# binary_watch.net
KiCad netlist of a schematic drawn in EAGLE
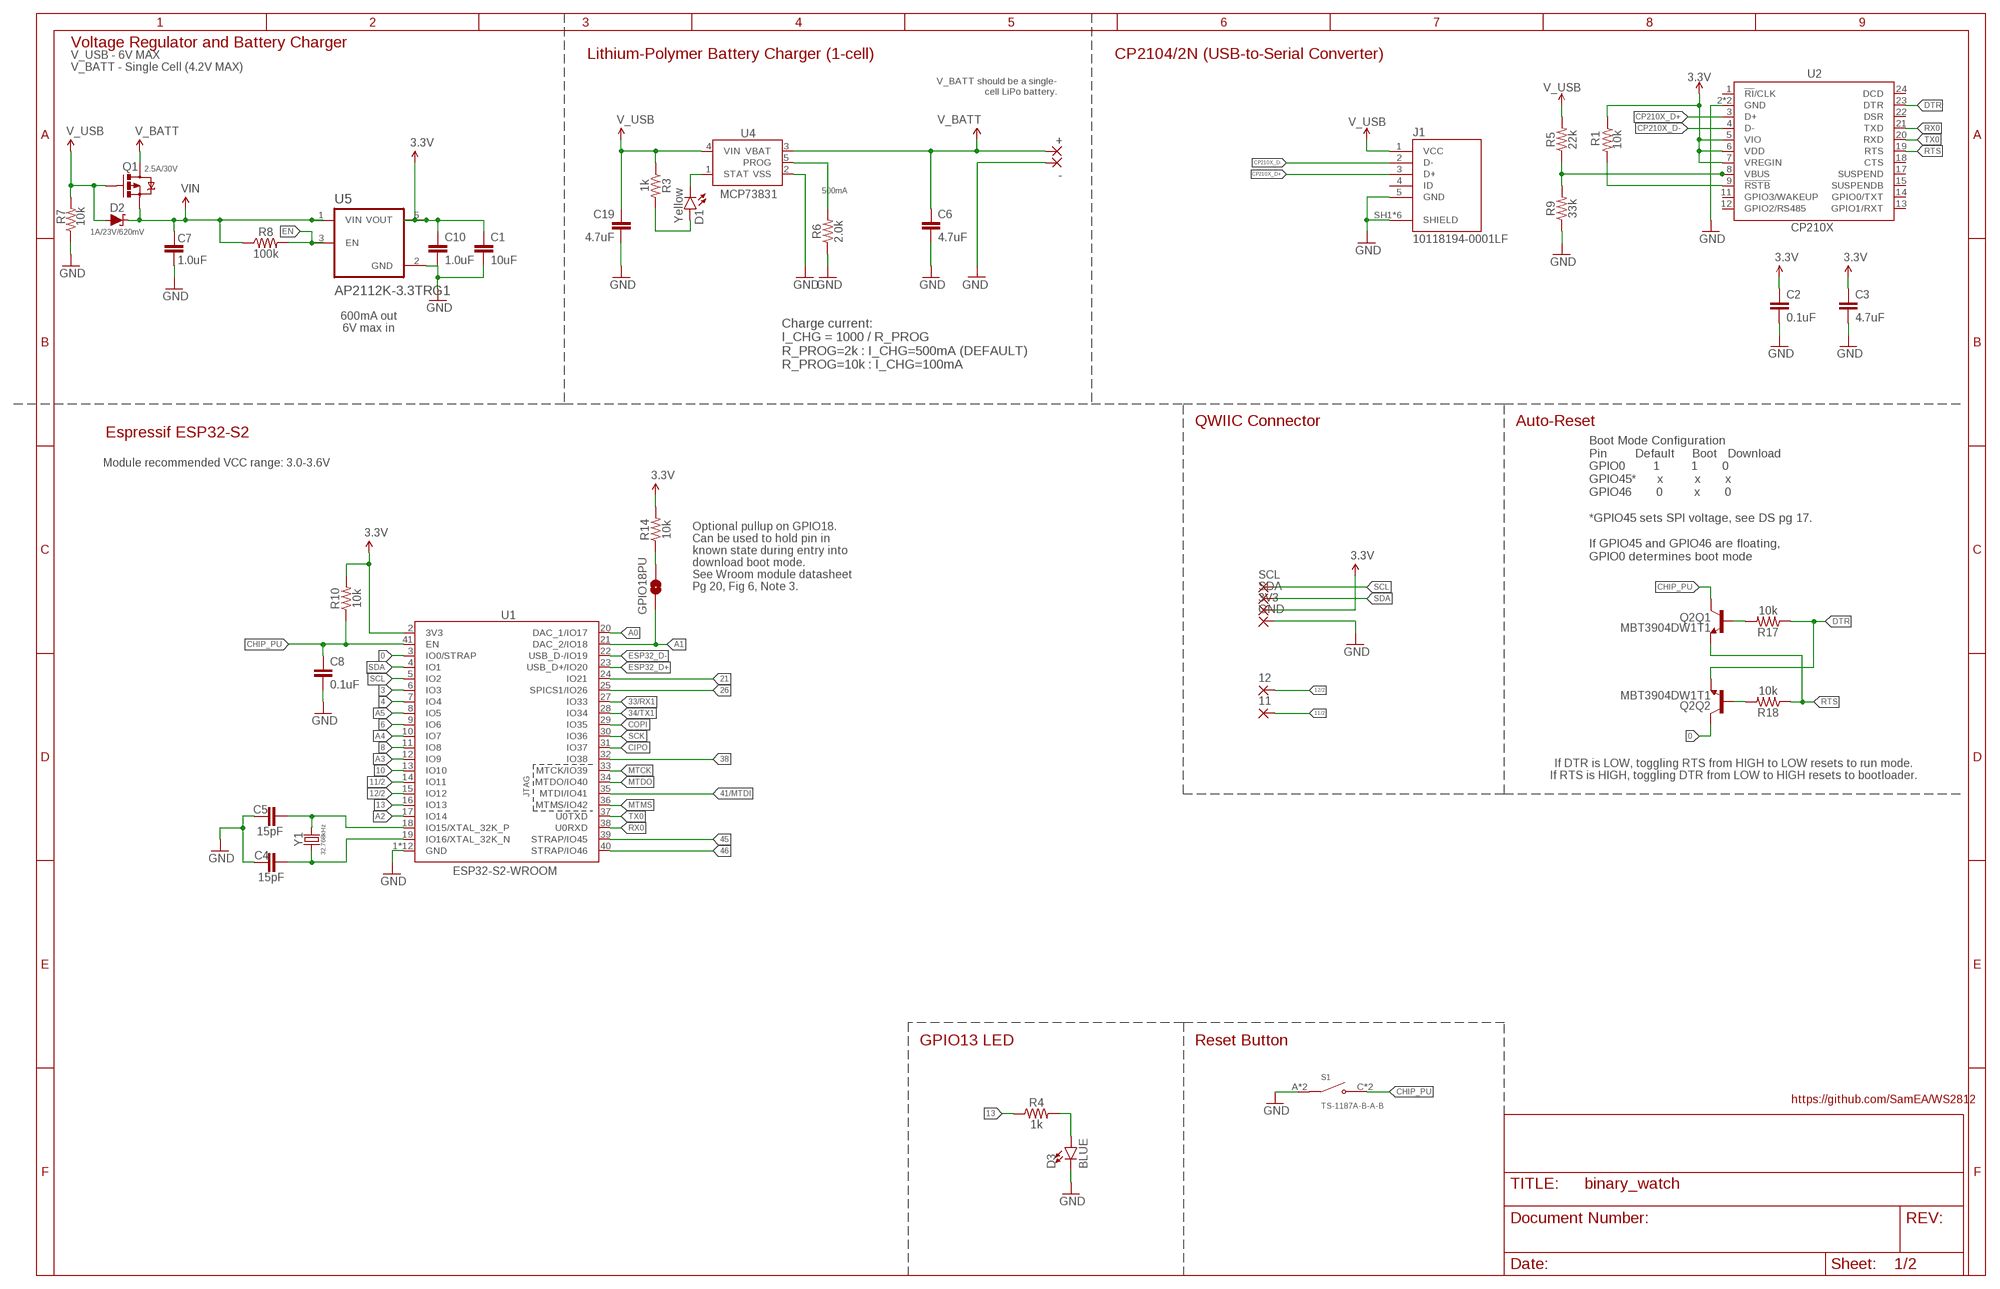
[diagram p0: schematic, sheet 1]
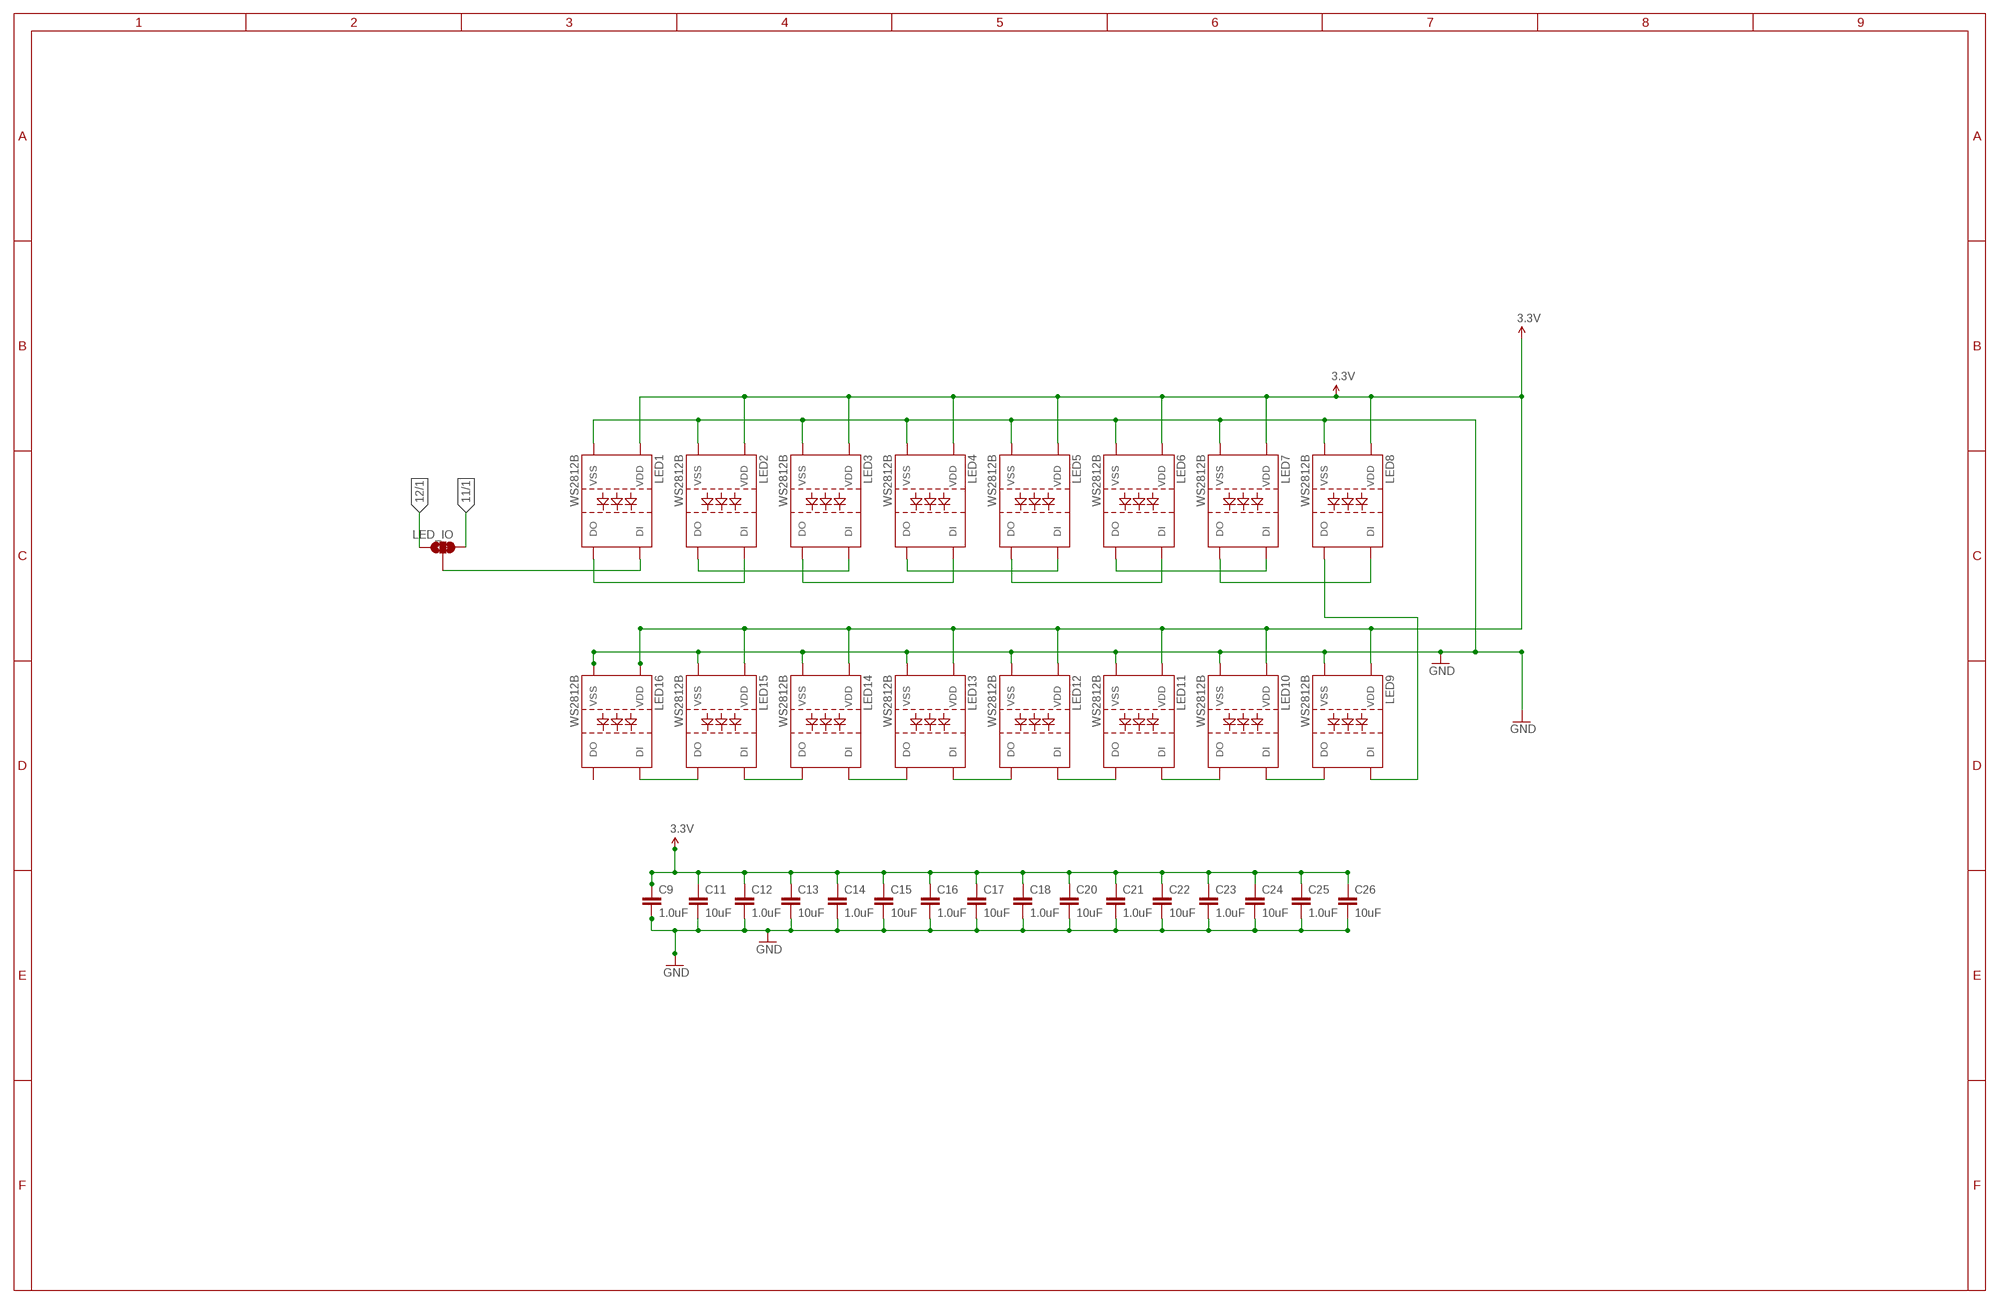
[diagram p1: schematic, sheet 2]

(export (version "E")
  (design (tool "Eeschema 10.0.6"))
  (components
    (comp (ref "+")
      (value "WIREPAD1,6/0,8")
      (footprint "eagle-import:1,6_0,8")
      (libsource (lib "eagle-import") (part "WIREPAD1,6/0,8"))
    )
    (comp (ref "-")
      (value "WIREPAD1,6/0,8")
      (footprint "eagle-import:1,6_0,8")
      (libsource (lib "eagle-import") (part "WIREPAD1,6/0,8"))
    )
    (comp (ref "3V3")
      (value "1,6/0,8")
      (footprint "eagle-import:1,6_0,8")
      (libsource (lib "eagle-import") (part "1,6/0,8"))
    )
    (comp (ref "11")
      (value "1,6/0,8")
      (footprint "eagle-import:1,6_0,8")
      (libsource (lib "eagle-import") (part "1,6/0,8"))
    )
    (comp (ref "12")
      (value "1,6/0,8")
      (footprint "eagle-import:1,6_0,8")
      (libsource (lib "eagle-import") (part "1,6/0,8"))
    )
    (comp (ref "C1")
      (value "10uF")
      (footprint "eagle-import:0402-TIGHT")
      (libsource (lib "eagle-import") (part "10UF-0402T-6.3V-20%"))
    )
    (comp (ref "C2")
      (value "0.1uF")
      (footprint "eagle-import:0402-TIGHT")
      (libsource (lib "eagle-import") (part "0.1UF-0402T-16V-10%"))
    )
    (comp (ref "C3")
      (value "4.7uF")
      (footprint "eagle-import:0402-TIGHT")
      (libsource (lib "eagle-import") (part "4.7UF-0402_TIGHT-6.3V-20%-X5R"))
    )
    (comp (ref "C4")
      (value "15pF")
      (footprint "eagle-import:0402-TIGHT")
      (libsource (lib "eagle-import") (part "15PF-0402T-50V-5%"))
    )
    (comp (ref "C5")
      (value "15pF")
      (footprint "eagle-import:0402-TIGHT")
      (libsource (lib "eagle-import") (part "15PF-0402T-50V-5%"))
    )
    (comp (ref "C6")
      (value "4.7uF")
      (footprint "eagle-import:0402-TIGHT")
      (libsource (lib "eagle-import") (part "4.7UF-0402_TIGHT-6.3V-20%-X5R"))
    )
    (comp (ref "C7")
      (value "1.0uF")
      (footprint "eagle-import:0402-TIGHT")
      (libsource (lib "eagle-import") (part "1.0UF-0402T-16V-10%"))
    )
    (comp (ref "C8")
      (value "0.1uF")
      (footprint "eagle-import:0402-TIGHT")
      (libsource (lib "eagle-import") (part "0.1UF-0402T-16V-10%"))
    )
    (comp (ref "C10")
      (value "1.0uF")
      (footprint "eagle-import:0402-TIGHT")
      (libsource (lib "eagle-import") (part "1.0UF-0402T-16V-10%"))
    )
    (comp (ref "C19")
      (value "4.7uF")
      (footprint "eagle-import:0402-TIGHT")
      (libsource (lib "eagle-import") (part "4.7UF-0402_TIGHT-6.3V-20%-X5R"))
    )
    (comp (ref "D1")
      (value "Yellow")
      (footprint "eagle-import:LED-0603")
      (libsource (lib "eagle-import") (part "LED-YELLOW0603"))
    )
    (comp (ref "D2")
      (value "1A/23V/620mV")
      (footprint "eagle-import:SOD-323")
      (libsource (lib "eagle-import") (part "DIODE-SCHOTTKY-BAT20J"))
    )
    (comp (ref "D3")
      (value "BLUE")
      (footprint "eagle-import:LED-0603")
      (libsource (lib "eagle-import") (part "LED-BLUE0603"))
    )
    (comp (ref "GND")
      (value "1,6/0,8")
      (footprint "eagle-import:1,6_0,8")
      (libsource (lib "eagle-import") (part "1,6/0,8"))
    )
    (comp (ref "GPIO18PU")
      (value "JUMPER-SMT_2_NO_SILK")
      (footprint "eagle-import:SMT-JUMPER_2_NO_SILK")
      (libsource (lib "eagle-import") (part "JUMPER-SMT_2_NO_SILK"))
    )
    (comp (ref "J1")
      (value "10118194-0001LF")
      (footprint "eagle-import:AMPHENOL_10118194-0001LF")
      (fields (field (name "MF") "Amphenol ICC"))
      (libsource (lib "eagle-import") (part "10118194-0001LF"))
    )
    (comp (ref "Q1")
      (value "2.5A/30V")
      (footprint "eagle-import:SOT23-3@1")
      (libsource (lib "eagle-import") (part "MOSFET-PCHANNELDMG2307L"))
    )
    (comp (ref "Q2")
      (value "MBT3904DW1T1")
      (footprint "eagle-import:SC70-6")
      (libsource (lib "eagle-import") (part "TRANS_NPN_DUAL-MBT3904DW1T1"))
    )
    (comp (ref "R1")
      (value "10k")
      (footprint "eagle-import:0402-TIGHT")
      (libsource (lib "eagle-import") (part "10KOHM-0402T-1/16W-1%"))
    )
    (comp (ref "R3")
      (value "1k")
      (footprint "eagle-import:0402-TIGHT")
      (libsource (lib "eagle-import") (part "1KOHM-0402T-1/16W-1%"))
    )
    (comp (ref "R4")
      (value "1k")
      (footprint "eagle-import:0402-TIGHT")
      (libsource (lib "eagle-import") (part "1KOHM-0402T-1/16W-1%"))
    )
    (comp (ref "R5")
      (value "22k")
      (footprint "eagle-import:0402-TIGHT")
      (libsource (lib "eagle-import") (part "22KOHM-0402_TIGHT-1/10W-1%"))
    )
    (comp (ref "R6")
      (value "2.0k")
      (footprint "eagle-import:0603")
      (libsource (lib "eagle-import") (part "2.0KOHM1/10W5%(0603)"))
    )
    (comp (ref "R7")
      (value "10k")
      (footprint "eagle-import:0402-TIGHT")
      (libsource (lib "eagle-import") (part "10KOHM-0402T-1/16W-1%"))
    )
    (comp (ref "R8")
      (value "100k")
      (footprint "eagle-import:0402-TIGHT")
      (libsource (lib "eagle-import") (part "100KOHM-0402T-1/16W-1%"))
    )
    (comp (ref "R9")
      (value "33k")
      (footprint "eagle-import:0402-TIGHT")
      (libsource (lib "eagle-import") (part "33KOHM-0402T-1/16W-1%"))
    )
    (comp (ref "R10")
      (value "10k")
      (footprint "eagle-import:0402-TIGHT")
      (libsource (lib "eagle-import") (part "10KOHM-0402T-1/16W-1%"))
    )
    (comp (ref "R14")
      (value "10k")
      (footprint "eagle-import:0402-TIGHT")
      (libsource (lib "eagle-import") (part "10KOHM-0402T-1/16W-1%"))
    )
    (comp (ref "R17")
      (value "10k")
      (footprint "eagle-import:0402-TIGHT")
      (libsource (lib "eagle-import") (part "10KOHM-0402T-1/16W-1%"))
    )
    (comp (ref "R18")
      (value "10k")
      (footprint "eagle-import:0402-TIGHT")
      (libsource (lib "eagle-import") (part "10KOHM-0402T-1/16W-1%"))
    )
    (comp (ref "S1")
      (value "TS-1187A-B-A-B")
      (footprint "eagle-import:SW_TS-1187A-B-A-B")
      (fields (field (name "MF") "XKB Industrial Precision"))
      (libsource (lib "eagle-import") (part "TS-1187A-B-A-B"))
    )
    (comp (ref "SCL")
      (value "1,6/0,8")
      (footprint "eagle-import:1,6_0,8")
      (libsource (lib "eagle-import") (part "1,6/0,8"))
    )
    (comp (ref "SDA")
      (value "1,6/0,8")
      (footprint "eagle-import:1,6_0,8")
      (libsource (lib "eagle-import") (part "1,6/0,8"))
    )
    (comp (ref "U1")
      (value "ESP32-S2-WROOM")
      (footprint "eagle-import:ESP32-S2-WROOM")
      (libsource (lib "eagle-import") (part "ESP32-S2-WROOM"))
    )
    (comp (ref "U2")
      (value "CP210X")
      (footprint "eagle-import:QFN24")
      (libsource (lib "eagle-import") (part "CP2102N"))
    )
    (comp (ref "U4")
      (value "MCP73831")
      (footprint "eagle-import:SOT23-5")
      (libsource (lib "eagle-import") (part "MCP73831"))
    )
    (comp (ref "U5")
      (value "AP2112K-3.3TRG1")
      (footprint "eagle-import:SOT95P285X140-5N")
      (fields (field (name "MF") "Diodes Inc."))
      (libsource (lib "eagle-import") (part "AP2112K-3.3TRG1"))
    )
    (comp (ref "Y1")
      (value "32.768kHz")
      (footprint "eagle-import:CRYSTAL-SMD-3.2X1.5MM")
      (libsource (lib "eagle-import") (part "CRYSTAL-32.768KHZSMD-3.2X1.5"))
    )
    (comp (ref "C9")
      (value "1.0uF")
      (footprint "eagle-import:0402-TIGHT")
      (libsource (lib "eagle-import") (part "1.0UF-0402T-16V-10%"))
    )
    (comp (ref "C11")
      (value "10uF")
      (footprint "eagle-import:0402-TIGHT")
      (libsource (lib "eagle-import") (part "10UF-0402T-6.3V-20%"))
    )
    (comp (ref "C12")
      (value "1.0uF")
      (footprint "eagle-import:0402-TIGHT")
      (libsource (lib "eagle-import") (part "1.0UF-0402T-16V-10%"))
    )
    (comp (ref "C13")
      (value "10uF")
      (footprint "eagle-import:0402-TIGHT")
      (libsource (lib "eagle-import") (part "10UF-0402T-6.3V-20%"))
    )
    (comp (ref "C14")
      (value "1.0uF")
      (footprint "eagle-import:0402-TIGHT")
      (libsource (lib "eagle-import") (part "1.0UF-0402T-16V-10%"))
    )
    (comp (ref "C15")
      (value "10uF")
      (footprint "eagle-import:0402-TIGHT")
      (libsource (lib "eagle-import") (part "10UF-0402T-6.3V-20%"))
    )
    (comp (ref "C16")
      (value "1.0uF")
      (footprint "eagle-import:0402-TIGHT")
      (libsource (lib "eagle-import") (part "1.0UF-0402T-16V-10%"))
    )
    (comp (ref "C17")
      (value "10uF")
      (footprint "eagle-import:0402-TIGHT")
      (libsource (lib "eagle-import") (part "10UF-0402T-6.3V-20%"))
    )
    (comp (ref "C18")
      (value "1.0uF")
      (footprint "eagle-import:0402-TIGHT")
      (libsource (lib "eagle-import") (part "1.0UF-0402T-16V-10%"))
    )
    (comp (ref "C20")
      (value "10uF")
      (footprint "eagle-import:0402-TIGHT")
      (libsource (lib "eagle-import") (part "10UF-0402T-6.3V-20%"))
    )
    (comp (ref "C21")
      (value "1.0uF")
      (footprint "eagle-import:0402-TIGHT")
      (libsource (lib "eagle-import") (part "1.0UF-0402T-16V-10%"))
    )
    (comp (ref "C22")
      (value "10uF")
      (footprint "eagle-import:0402-TIGHT")
      (libsource (lib "eagle-import") (part "10UF-0402T-6.3V-20%"))
    )
    (comp (ref "C23")
      (value "1.0uF")
      (footprint "eagle-import:0402-TIGHT")
      (libsource (lib "eagle-import") (part "1.0UF-0402T-16V-10%"))
    )
    (comp (ref "C24")
      (value "10uF")
      (footprint "eagle-import:0402-TIGHT")
      (libsource (lib "eagle-import") (part "10UF-0402T-6.3V-20%"))
    )
    (comp (ref "C25")
      (value "1.0uF")
      (footprint "eagle-import:0402-TIGHT")
      (libsource (lib "eagle-import") (part "1.0UF-0402T-16V-10%"))
    )
    (comp (ref "C26")
      (value "10uF")
      (footprint "eagle-import:0402-TIGHT")
      (libsource (lib "eagle-import") (part "10UF-0402T-6.3V-20%"))
    )
    (comp (ref "LED1")
      (value "WS2812B")
      (footprint "eagle-import:WS2812B")
      (libsource (lib "eagle-import") (part "WS2812B"))
    )
    (comp (ref "LED2")
      (value "WS2812B")
      (footprint "eagle-import:WS2812B")
      (libsource (lib "eagle-import") (part "WS2812B"))
    )
    (comp (ref "LED3")
      (value "WS2812B")
      (footprint "eagle-import:WS2812B")
      (libsource (lib "eagle-import") (part "WS2812B"))
    )
    (comp (ref "LED4")
      (value "WS2812B")
      (footprint "eagle-import:WS2812B")
      (libsource (lib "eagle-import") (part "WS2812B"))
    )
    (comp (ref "LED5")
      (value "WS2812B")
      (footprint "eagle-import:WS2812B")
      (libsource (lib "eagle-import") (part "WS2812B"))
    )
    (comp (ref "LED6")
      (value "WS2812B")
      (footprint "eagle-import:WS2812B")
      (libsource (lib "eagle-import") (part "WS2812B"))
    )
    (comp (ref "LED7")
      (value "WS2812B")
      (footprint "eagle-import:WS2812B")
      (libsource (lib "eagle-import") (part "WS2812B"))
    )
    (comp (ref "LED8")
      (value "WS2812B")
      (footprint "eagle-import:WS2812B")
      (libsource (lib "eagle-import") (part "WS2812B"))
    )
    (comp (ref "LED9")
      (value "WS2812B")
      (footprint "eagle-import:WS2812B")
      (libsource (lib "eagle-import") (part "WS2812B"))
    )
    (comp (ref "LED10")
      (value "WS2812B")
      (footprint "eagle-import:WS2812B")
      (libsource (lib "eagle-import") (part "WS2812B"))
    )
    (comp (ref "LED11")
      (value "WS2812B")
      (footprint "eagle-import:WS2812B")
      (libsource (lib "eagle-import") (part "WS2812B"))
    )
    (comp (ref "LED12")
      (value "WS2812B")
      (footprint "eagle-import:WS2812B")
      (libsource (lib "eagle-import") (part "WS2812B"))
    )
    (comp (ref "LED13")
      (value "WS2812B")
      (footprint "eagle-import:WS2812B")
      (libsource (lib "eagle-import") (part "WS2812B"))
    )
    (comp (ref "LED14")
      (value "WS2812B")
      (footprint "eagle-import:WS2812B")
      (libsource (lib "eagle-import") (part "WS2812B"))
    )
    (comp (ref "LED15")
      (value "WS2812B")
      (footprint "eagle-import:WS2812B")
      (libsource (lib "eagle-import") (part "WS2812B"))
    )
    (comp (ref "LED16")
      (value "WS2812B")
      (footprint "eagle-import:WS2812B")
      (libsource (lib "eagle-import") (part "WS2812B"))
    )
    (comp (ref "LED_IO")
      (value "JUMPER-SMT_3_1-NC_TRACE_SILK")
      (footprint "eagle-import:SMT-JUMPER_3_1-NC_TRACE_SILK")
      (libsource (lib "eagle-import") (part "JUMPER-SMT_3_1-NC_TRACE_SILK"))
    )
  )
  (nets
    (net (code "1") (name "0") (class "Default")
      (node (ref "Q2") (pin "6") (pinfunction "C_6") (pintype "passive"))
      (node (ref "U1") (pin "3") (pinfunction "IO0/STRAP_3") (pintype "bidirectional"))
    )
    (net (code "2") (name "3") (class "Default")
      (node (ref "U1") (pin "6") (pinfunction "IO3_6") (pintype "bidirectional"))
    )
    (net (code "3") (name "3.3V") (class "Default")
      (node (ref "3V3") (pin "1") (pinfunction "P_1") (pintype "passive"))
      (node (ref "C1") (pin "1") (pinfunction "1_1") (pintype "passive"))
      (node (ref "C10") (pin "1") (pinfunction "1_1") (pintype "passive"))
      (node (ref "C11") (pin "1") (pinfunction "1_1") (pintype "passive"))
      (node (ref "C12") (pin "1") (pinfunction "1_1") (pintype "passive"))
      (node (ref "C13") (pin "1") (pinfunction "1_1") (pintype "passive"))
      (node (ref "C14") (pin "1") (pinfunction "1_1") (pintype "passive"))
      (node (ref "C15") (pin "1") (pinfunction "1_1") (pintype "passive"))
      (node (ref "C16") (pin "1") (pinfunction "1_1") (pintype "passive"))
      (node (ref "C17") (pin "1") (pinfunction "1_1") (pintype "passive"))
      (node (ref "C18") (pin "1") (pinfunction "1_1") (pintype "passive"))
      (node (ref "C2") (pin "1") (pinfunction "1_1") (pintype "passive"))
      (node (ref "C20") (pin "1") (pinfunction "1_1") (pintype "passive"))
      (node (ref "C21") (pin "1") (pinfunction "1_1") (pintype "passive"))
      (node (ref "C22") (pin "1") (pinfunction "1_1") (pintype "passive"))
      (node (ref "C23") (pin "1") (pinfunction "1_1") (pintype "passive"))
      (node (ref "C24") (pin "1") (pinfunction "1_1") (pintype "passive"))
      (node (ref "C25") (pin "1") (pinfunction "1_1") (pintype "passive"))
      (node (ref "C26") (pin "1") (pinfunction "1_1") (pintype "passive"))
      (node (ref "C3") (pin "1") (pinfunction "1_1") (pintype "passive"))
      (node (ref "C9") (pin "1") (pinfunction "1_1") (pintype "passive"))
      (node (ref "LED1") (pin "1") (pinfunction "VDD_1") (pintype "bidirectional"))
      (node (ref "LED10") (pin "1") (pinfunction "VDD_1") (pintype "bidirectional"))
      (node (ref "LED11") (pin "1") (pinfunction "VDD_1") (pintype "bidirectional"))
      (node (ref "LED12") (pin "1") (pinfunction "VDD_1") (pintype "bidirectional"))
      (node (ref "LED13") (pin "1") (pinfunction "VDD_1") (pintype "bidirectional"))
      (node (ref "LED14") (pin "1") (pinfunction "VDD_1") (pintype "bidirectional"))
      (node (ref "LED15") (pin "1") (pinfunction "VDD_1") (pintype "bidirectional"))
      (node (ref "LED16") (pin "1") (pinfunction "VDD_1") (pintype "bidirectional"))
      (node (ref "LED2") (pin "1") (pinfunction "VDD_1") (pintype "bidirectional"))
      (node (ref "LED3") (pin "1") (pinfunction "VDD_1") (pintype "bidirectional"))
      (node (ref "LED4") (pin "1") (pinfunction "VDD_1") (pintype "bidirectional"))
      (node (ref "LED5") (pin "1") (pinfunction "VDD_1") (pintype "bidirectional"))
      (node (ref "LED6") (pin "1") (pinfunction "VDD_1") (pintype "bidirectional"))
      (node (ref "LED7") (pin "1") (pinfunction "VDD_1") (pintype "bidirectional"))
      (node (ref "LED8") (pin "1") (pinfunction "VDD_1") (pintype "bidirectional"))
      (node (ref "LED9") (pin "1") (pinfunction "VDD_1") (pintype "bidirectional"))
      (node (ref "R1") (pin "1") (pinfunction "1_1") (pintype "passive"))
      (node (ref "R10") (pin "2") (pinfunction "2_2") (pintype "passive"))
      (node (ref "R14") (pin "2") (pinfunction "2_2") (pintype "passive"))
      (node (ref "U1") (pin "2") (pinfunction "3V3_2") (pintype "bidirectional"))
      (node (ref "U2") (pin "5") (pinfunction "VIO_5") (pintype "bidirectional"))
      (node (ref "U2") (pin "6") (pinfunction "VDD_6") (pintype "bidirectional"))
      (node (ref "U2") (pin "7") (pinfunction "VREGIN_7") (pintype "bidirectional"))
      (node (ref "U5") (pin "5") (pinfunction "VOUT_5") (pintype "power_in"))
    )
    (net (code "4") (name "4") (class "Default")
      (node (ref "U1") (pin "7") (pinfunction "IO4_7") (pintype "bidirectional"))
    )
    (net (code "5") (name "6") (class "Default")
      (node (ref "U1") (pin "9") (pinfunction "IO6_9") (pintype "bidirectional"))
    )
    (net (code "6") (name "8") (class "Default")
      (node (ref "U1") (pin "11") (pinfunction "IO8_11") (pintype "bidirectional"))
    )
    (net (code "7") (name "10") (class "Default")
      (node (ref "U1") (pin "13") (pinfunction "IO10_13") (pintype "bidirectional"))
    )
    (net (code "8") (name "11") (class "Default")
      (node (ref "11") (pin "1") (pinfunction "P_1") (pintype "passive"))
      (node (ref "LED_IO") (pin "3") (pinfunction "3_3") (pintype "passive"))
      (node (ref "U1") (pin "14") (pinfunction "IO11_14") (pintype "bidirectional"))
    )
    (net (code "9") (name "12") (class "Default")
      (node (ref "12") (pin "1") (pinfunction "P_1") (pintype "passive"))
      (node (ref "LED_IO") (pin "1") (pinfunction "1_1") (pintype "passive"))
      (node (ref "U1") (pin "15") (pinfunction "IO12_15") (pintype "bidirectional"))
    )
    (net (code "10") (name "13") (class "Default")
      (node (ref "R4") (pin "1") (pinfunction "1_1") (pintype "passive"))
      (node (ref "U1") (pin "16") (pinfunction "IO13_16") (pintype "bidirectional"))
    )
    (net (code "11") (name "21") (class "Default")
      (node (ref "U1") (pin "24") (pinfunction "IO21_24") (pintype "bidirectional"))
    )
    (net (code "12") (name "26") (class "Default")
      (node (ref "U1") (pin "25") (pinfunction "SPICS1/IO26_25") (pintype "bidirectional"))
    )
    (net (code "13") (name "33{slash}RX1") (class "Default")
      (node (ref "U1") (pin "27") (pinfunction "IO33_27") (pintype "bidirectional"))
    )
    (net (code "14") (name "34{slash}TX1") (class "Default")
      (node (ref "U1") (pin "28") (pinfunction "IO34_28") (pintype "bidirectional"))
    )
    (net (code "15") (name "38") (class "Default")
      (node (ref "U1") (pin "32") (pinfunction "IO38_32") (pintype "bidirectional"))
    )
    (net (code "16") (name "41{slash}MTDI") (class "Default")
      (node (ref "U1") (pin "35") (pinfunction "MTDI/IO41_35") (pintype "bidirectional"))
    )
    (net (code "17") (name "45") (class "Default")
      (node (ref "U1") (pin "39") (pinfunction "STRAP/IO45_39") (pintype "bidirectional"))
    )
    (net (code "18") (name "46") (class "Default")
      (node (ref "U1") (pin "40") (pinfunction "STRAP/IO46_40") (pintype "bidirectional"))
    )
    (net (code "19") (name "A0") (class "Default")
      (node (ref "U1") (pin "20") (pinfunction "DAC_1/IO17_20") (pintype "bidirectional"))
    )
    (net (code "20") (name "A1") (class "Default")
      (node (ref "GPIO18PU") (pin "1") (pinfunction "1_1") (pintype "passive"))
      (node (ref "U1") (pin "21") (pinfunction "DAC_2/IO18_21") (pintype "bidirectional"))
    )
    (net (code "21") (name "A2") (class "Default")
      (node (ref "U1") (pin "17") (pinfunction "IO14_17") (pintype "bidirectional"))
    )
    (net (code "22") (name "A3") (class "Default")
      (node (ref "U1") (pin "12") (pinfunction "IO9_12") (pintype "bidirectional"))
    )
    (net (code "23") (name "A4") (class "Default")
      (node (ref "U1") (pin "10") (pinfunction "IO7_10") (pintype "bidirectional"))
    )
    (net (code "24") (name "A5") (class "Default")
      (node (ref "U1") (pin "8") (pinfunction "IO5_8") (pintype "bidirectional"))
    )
    (net (code "25") (name "CHIP_PU") (class "Default")
      (node (ref "C8") (pin "1") (pinfunction "1_1") (pintype "passive"))
      (node (ref "Q2") (pin "3") (pinfunction "C_3") (pintype "passive"))
      (node (ref "R10") (pin "1") (pinfunction "1_1") (pintype "passive"))
      (node (ref "S1") (pin "C") (pinfunction "NO_C") (pintype "passive"))
      (node (ref "S1") (pin "D") (pinfunction "NO_D") (pintype "passive"))
      (node (ref "U1") (pin "41") (pinfunction "EN_41") (pintype "bidirectional"))
    )
    (net (code "26") (name "CIPO") (class "Default")
      (node (ref "U1") (pin "31") (pinfunction "IO37_31") (pintype "bidirectional"))
    )
    (net (code "27") (name "COPI") (class "Default")
      (node (ref "U1") (pin "29") (pinfunction "IO35_29") (pintype "bidirectional"))
    )
    (net (code "28") (name "CP210X_D+") (class "Default")
      (node (ref "J1") (pin "3") (pinfunction "D+_3") (pintype "bidirectional"))
      (node (ref "U2") (pin "3") (pinfunction "D+_3") (pintype "bidirectional"))
    )
    (net (code "29") (name "CP210X_D-") (class "Default")
      (node (ref "J1") (pin "2") (pinfunction "D-_2") (pintype "bidirectional"))
      (node (ref "U2") (pin "4") (pinfunction "D-_4") (pintype "bidirectional"))
    )
    (net (code "30") (name "DTR") (class "Default")
      (node (ref "Q2") (pin "1") (pinfunction "E_1") (pintype "passive"))
      (node (ref "R17") (pin "1") (pinfunction "1_1") (pintype "passive"))
      (node (ref "U2") (pin "23") (pinfunction "DTR_23") (pintype "bidirectional"))
    )
    (net (code "31") (name "EN") (class "Default")
      (node (ref "R8") (pin "2") (pinfunction "2_2") (pintype "passive"))
      (node (ref "U5") (pin "3") (pinfunction "EN_3") (pintype "input"))
    )
    (net (code "32") (name "ESP32_D+") (class "Default")
      (node (ref "U1") (pin "23") (pinfunction "USB_D+/IO20_23") (pintype "bidirectional"))
    )
    (net (code "33") (name "ESP32_D-") (class "Default")
      (node (ref "U1") (pin "22") (pinfunction "USB_D-/IO19_22") (pintype "bidirectional"))
    )
    (net (code "34") (name "GND") (class "Default")
      (node (ref "-") (pin "1") (pinfunction "P_1") (pintype "passive"))
      (node (ref "C1") (pin "2") (pinfunction "2_2") (pintype "passive"))
      (node (ref "C10") (pin "2") (pinfunction "2_2") (pintype "passive"))
      (node (ref "C11") (pin "2") (pinfunction "2_2") (pintype "passive"))
      (node (ref "C12") (pin "2") (pinfunction "2_2") (pintype "passive"))
      (node (ref "C13") (pin "2") (pinfunction "2_2") (pintype "passive"))
      (node (ref "C14") (pin "2") (pinfunction "2_2") (pintype "passive"))
      (node (ref "C15") (pin "2") (pinfunction "2_2") (pintype "passive"))
      (node (ref "C16") (pin "2") (pinfunction "2_2") (pintype "passive"))
      (node (ref "C17") (pin "2") (pinfunction "2_2") (pintype "passive"))
      (node (ref "C18") (pin "2") (pinfunction "2_2") (pintype "passive"))
      (node (ref "C19") (pin "2") (pinfunction "2_2") (pintype "passive"))
      (node (ref "C2") (pin "2") (pinfunction "2_2") (pintype "passive"))
      (node (ref "C20") (pin "2") (pinfunction "2_2") (pintype "passive"))
      (node (ref "C21") (pin "2") (pinfunction "2_2") (pintype "passive"))
      (node (ref "C22") (pin "2") (pinfunction "2_2") (pintype "passive"))
      (node (ref "C23") (pin "2") (pinfunction "2_2") (pintype "passive"))
      (node (ref "C24") (pin "2") (pinfunction "2_2") (pintype "passive"))
      (node (ref "C25") (pin "2") (pinfunction "2_2") (pintype "passive"))
      (node (ref "C26") (pin "2") (pinfunction "2_2") (pintype "passive"))
      (node (ref "C3") (pin "2") (pinfunction "2_2") (pintype "passive"))
      (node (ref "C4") (pin "1") (pinfunction "1_1") (pintype "passive"))
      (node (ref "C5") (pin "1") (pinfunction "1_1") (pintype "passive"))
      (node (ref "C6") (pin "2") (pinfunction "2_2") (pintype "passive"))
      (node (ref "C7") (pin "2") (pinfunction "2_2") (pintype "passive"))
      (node (ref "C8") (pin "2") (pinfunction "2_2") (pintype "passive"))
      (node (ref "C9") (pin "2") (pinfunction "2_2") (pintype "passive"))
      (node (ref "D3") (pin "C") (pinfunction "C_C") (pintype "passive"))
      (node (ref "GND") (pin "1") (pinfunction "P_1") (pintype "passive"))
      (node (ref "J1") (pin "5") (pinfunction "GND_5") (pintype "power_in"))
      (node (ref "J1") (pin "SH1") (pinfunction "SHIELD_SH1") (pintype "passive"))
      (node (ref "J1") (pin "SH2") (pinfunction "SHIELD_SH2") (pintype "passive"))
      (node (ref "J1") (pin "SH3") (pinfunction "SHIELD_SH3") (pintype "passive"))
      (node (ref "J1") (pin "SH4") (pinfunction "SHIELD_SH4") (pintype "passive"))
      (node (ref "J1") (pin "SH5") (pinfunction "SHIELD_SH5") (pintype "passive"))
      (node (ref "J1") (pin "SH6") (pinfunction "SHIELD_SH6") (pintype "passive"))
      (node (ref "LED1") (pin "3") (pinfunction "VSS_3") (pintype "bidirectional"))
      (node (ref "LED10") (pin "3") (pinfunction "VSS_3") (pintype "bidirectional"))
      (node (ref "LED11") (pin "3") (pinfunction "VSS_3") (pintype "bidirectional"))
      (node (ref "LED12") (pin "3") (pinfunction "VSS_3") (pintype "bidirectional"))
      (node (ref "LED13") (pin "3") (pinfunction "VSS_3") (pintype "bidirectional"))
      (node (ref "LED14") (pin "3") (pinfunction "VSS_3") (pintype "bidirectional"))
      (node (ref "LED15") (pin "3") (pinfunction "VSS_3") (pintype "bidirectional"))
      (node (ref "LED16") (pin "3") (pinfunction "VSS_3") (pintype "bidirectional"))
      (node (ref "LED2") (pin "3") (pinfunction "VSS_3") (pintype "bidirectional"))
      (node (ref "LED3") (pin "3") (pinfunction "VSS_3") (pintype "bidirectional"))
      (node (ref "LED4") (pin "3") (pinfunction "VSS_3") (pintype "bidirectional"))
      (node (ref "LED5") (pin "3") (pinfunction "VSS_3") (pintype "bidirectional"))
      (node (ref "LED6") (pin "3") (pinfunction "VSS_3") (pintype "bidirectional"))
      (node (ref "LED7") (pin "3") (pinfunction "VSS_3") (pintype "bidirectional"))
      (node (ref "LED8") (pin "3") (pinfunction "VSS_3") (pintype "bidirectional"))
      (node (ref "LED9") (pin "3") (pinfunction "VSS_3") (pintype "bidirectional"))
      (node (ref "R6") (pin "1") (pinfunction "1_1") (pintype "passive"))
      (node (ref "R7") (pin "1") (pinfunction "1_1") (pintype "passive"))
      (node (ref "R9") (pin "1") (pinfunction "1_1") (pintype "passive"))
      (node (ref "S1") (pin "A") (pinfunction "COM_A") (pintype "passive"))
      (node (ref "S1") (pin "B") (pinfunction "COM_B") (pintype "passive"))
      (node (ref "U1") (pin "1") (pinfunction "GND_1") (pintype "bidirectional"))
      (node (ref "U1") (pin "26") (pinfunction "GND_26") (pintype "bidirectional"))
      (node (ref "U1") (pin "42") (pinfunction "GND_42") (pintype "bidirectional"))
      (node (ref "U1") (pin "GNDEP0") (pinfunction "GND_GNDEP0") (pintype "bidirectional"))
      (node (ref "U1") (pin "GNDEP1") (pinfunction "GND_GNDEP1") (pintype "bidirectional"))
      (node (ref "U1") (pin "GNDEP2") (pinfunction "GND_GNDEP2") (pintype "bidirectional"))
      (node (ref "U1") (pin "GNDEP3") (pinfunction "GND_GNDEP3") (pintype "bidirectional"))
      (node (ref "U1") (pin "GNDEP4") (pinfunction "GND_GNDEP4") (pintype "bidirectional"))
      (node (ref "U1") (pin "GNDEP5") (pinfunction "GND_GNDEP5") (pintype "bidirectional"))
      (node (ref "U1") (pin "GNDEP6") (pinfunction "GND_GNDEP6") (pintype "bidirectional"))
      (node (ref "U1") (pin "GNDEP7") (pinfunction "GND_GNDEP7") (pintype "bidirectional"))
      (node (ref "U1") (pin "GNDEP8") (pinfunction "GND_GNDEP8") (pintype "bidirectional"))
      (node (ref "U2") (pin "2") (pinfunction "GND_2") (pintype "bidirectional"))
      (node (ref "U2") (pin "PAD") (pinfunction "GND_PAD") (pintype "bidirectional"))
      (node (ref "U4") (pin "2") (pinfunction "VSS_2") (pintype "power_in"))
      (node (ref "U5") (pin "2") (pinfunction "GND_2") (pintype "power_in"))
    )
    (net (code "35") (name "MTCK") (class "Default")
      (node (ref "U1") (pin "33") (pinfunction "MTCK/IO39_33") (pintype "bidirectional"))
    )
    (net (code "36") (name "MTDO") (class "Default")
      (node (ref "U1") (pin "34") (pinfunction "MTDO/IO40_34") (pintype "bidirectional"))
    )
    (net (code "37") (name "MTMS") (class "Default")
      (node (ref "U1") (pin "36") (pinfunction "MTMS/IO42_36") (pintype "bidirectional"))
    )
    (net (code "38") (name "Net-(D1-PadA)") (class "Default")
      (node (ref "D1") (pin "A") (pinfunction "A_A") (pintype "passive"))
      (node (ref "R3") (pin "2") (pinfunction "2_2") (pintype "passive"))
    )
    (net (code "39") (name "Net-(D3-PadA)") (class "Default")
      (node (ref "D3") (pin "A") (pinfunction "A_A") (pintype "passive"))
      (node (ref "R4") (pin "2") (pinfunction "2_2") (pintype "passive"))
    )
    (net (code "40") (name "Net-(GPIO18PU-Pad2)") (class "Default")
      (node (ref "GPIO18PU") (pin "2") (pinfunction "2_2") (pintype "passive"))
      (node (ref "R14") (pin "1") (pinfunction "1_1") (pintype "passive"))
    )
    (net (code "41") (name "Net-(LED1-DI)") (class "Default")
      (node (ref "LED1") (pin "4") (pinfunction "DI_4") (pintype "bidirectional"))
      (node (ref "LED_IO") (pin "2") (pinfunction "2_2") (pintype "passive"))
    )
    (net (code "42") (name "Net-(LED1-DO)") (class "Default")
      (node (ref "LED1") (pin "2") (pinfunction "DO_2") (pintype "bidirectional"))
      (node (ref "LED2") (pin "4") (pinfunction "DI_4") (pintype "bidirectional"))
    )
    (net (code "43") (name "Net-(LED2-DO)") (class "Default")
      (node (ref "LED2") (pin "2") (pinfunction "DO_2") (pintype "bidirectional"))
      (node (ref "LED3") (pin "4") (pinfunction "DI_4") (pintype "bidirectional"))
    )
    (net (code "44") (name "Net-(LED3-DO)") (class "Default")
      (node (ref "LED3") (pin "2") (pinfunction "DO_2") (pintype "bidirectional"))
      (node (ref "LED4") (pin "4") (pinfunction "DI_4") (pintype "bidirectional"))
    )
    (net (code "45") (name "Net-(LED4-DO)") (class "Default")
      (node (ref "LED4") (pin "2") (pinfunction "DO_2") (pintype "bidirectional"))
      (node (ref "LED5") (pin "4") (pinfunction "DI_4") (pintype "bidirectional"))
    )
    (net (code "46") (name "Net-(LED5-DO)") (class "Default")
      (node (ref "LED5") (pin "2") (pinfunction "DO_2") (pintype "bidirectional"))
      (node (ref "LED6") (pin "4") (pinfunction "DI_4") (pintype "bidirectional"))
    )
    (net (code "47") (name "Net-(LED6-DO)") (class "Default")
      (node (ref "LED6") (pin "2") (pinfunction "DO_2") (pintype "bidirectional"))
      (node (ref "LED7") (pin "4") (pinfunction "DI_4") (pintype "bidirectional"))
    )
    (net (code "48") (name "Net-(LED7-DO)") (class "Default")
      (node (ref "LED7") (pin "2") (pinfunction "DO_2") (pintype "bidirectional"))
      (node (ref "LED8") (pin "4") (pinfunction "DI_4") (pintype "bidirectional"))
    )
    (net (code "49") (name "Net-(LED8-DO)") (class "Default")
      (node (ref "LED8") (pin "2") (pinfunction "DO_2") (pintype "bidirectional"))
      (node (ref "LED9") (pin "4") (pinfunction "DI_4") (pintype "bidirectional"))
    )
    (net (code "50") (name "Net-(LED10-DI)") (class "Default")
      (node (ref "LED10") (pin "4") (pinfunction "DI_4") (pintype "bidirectional"))
      (node (ref "LED9") (pin "2") (pinfunction "DO_2") (pintype "bidirectional"))
    )
    (net (code "51") (name "Net-(LED10-DO)") (class "Default")
      (node (ref "LED10") (pin "2") (pinfunction "DO_2") (pintype "bidirectional"))
      (node (ref "LED11") (pin "4") (pinfunction "DI_4") (pintype "bidirectional"))
    )
    (net (code "52") (name "Net-(LED11-DO)") (class "Default")
      (node (ref "LED11") (pin "2") (pinfunction "DO_2") (pintype "bidirectional"))
      (node (ref "LED12") (pin "4") (pinfunction "DI_4") (pintype "bidirectional"))
    )
    (net (code "53") (name "Net-(LED12-DO)") (class "Default")
      (node (ref "LED12") (pin "2") (pinfunction "DO_2") (pintype "bidirectional"))
      (node (ref "LED13") (pin "4") (pinfunction "DI_4") (pintype "bidirectional"))
    )
    (net (code "54") (name "Net-(LED13-DO)") (class "Default")
      (node (ref "LED13") (pin "2") (pinfunction "DO_2") (pintype "bidirectional"))
      (node (ref "LED14") (pin "4") (pinfunction "DI_4") (pintype "bidirectional"))
    )
    (net (code "55") (name "Net-(LED14-DO)") (class "Default")
      (node (ref "LED14") (pin "2") (pinfunction "DO_2") (pintype "bidirectional"))
      (node (ref "LED15") (pin "4") (pinfunction "DI_4") (pintype "bidirectional"))
    )
    (net (code "56") (name "Net-(LED15-DO)") (class "Default")
      (node (ref "LED15") (pin "2") (pinfunction "DO_2") (pintype "bidirectional"))
      (node (ref "LED16") (pin "4") (pinfunction "DI_4") (pintype "bidirectional"))
    )
    (net (code "57") (name "Net-(Q2A-B)") (class "Default")
      (node (ref "Q2") (pin "5") (pinfunction "B_5") (pintype "passive"))
      (node (ref "R17") (pin "2") (pinfunction "2_2") (pintype "passive"))
    )
    (net (code "58") (name "Net-(Q2B-B)") (class "Default")
      (node (ref "Q2") (pin "2") (pinfunction "B_2") (pintype "passive"))
      (node (ref "R18") (pin "2") (pinfunction "2_2") (pintype "passive"))
    )
    (net (code "59") (name "Net-(U1-IO15{slash}XTAL_32K_P)") (class "Default")
      (node (ref "C5") (pin "2") (pinfunction "2_2") (pintype "passive"))
      (node (ref "U1") (pin "18") (pinfunction "IO15/XTAL_32K_P_18") (pintype "bidirectional"))
      (node (ref "Y1") (pin "P$2") (pinfunction "2_P$2") (pintype "passive"))
    )
    (net (code "60") (name "Net-(U1-IO16{slash}XTAL_32K_N)") (class "Default")
      (node (ref "C4") (pin "2") (pinfunction "2_2") (pintype "passive"))
      (node (ref "U1") (pin "19") (pinfunction "IO16/XTAL_32K_N_19") (pintype "bidirectional"))
      (node (ref "Y1") (pin "P$1") (pinfunction "1_P$1") (pintype "passive"))
    )
    (net (code "61") (name "Net-(U2-VBUS)") (class "Default")
      (node (ref "R5") (pin "1") (pinfunction "1_1") (pintype "passive"))
      (node (ref "R9") (pin "2") (pinfunction "2_2") (pintype "passive"))
      (node (ref "U2") (pin "8") (pinfunction "VBUS_8") (pintype "bidirectional"))
    )
    (net (code "62") (name "Net-(U2-~{RSTB})") (class "Default")
      (node (ref "R1") (pin "2") (pinfunction "2_2") (pintype "passive"))
      (node (ref "U2") (pin "9") (pinfunction "~{RSTB}_9") (pintype "bidirectional"))
    )
    (net (code "63") (name "Net-(U4-PROG)") (class "Default")
      (node (ref "R6") (pin "2") (pinfunction "2_2") (pintype "passive"))
      (node (ref "U4") (pin "5") (pinfunction "PROG_5") (pintype "input"))
    )
    (net (code "64") (name "Net-(U4-STAT)") (class "Default")
      (node (ref "D1") (pin "C") (pinfunction "C_C") (pintype "passive"))
      (node (ref "U4") (pin "1") (pinfunction "STAT_1") (pintype "output"))
    )
    (net (code "65") (name "RTS") (class "Default")
      (node (ref "Q2") (pin "4") (pinfunction "E_4") (pintype "passive"))
      (node (ref "R18") (pin "1") (pinfunction "1_1") (pintype "passive"))
      (node (ref "U2") (pin "19") (pinfunction "RTS_19") (pintype "bidirectional"))
    )
    (net (code "66") (name "RX0") (class "Default")
      (node (ref "U1") (pin "38") (pinfunction "U0RXD_38") (pintype "bidirectional"))
      (node (ref "U2") (pin "21") (pinfunction "TXD_21") (pintype "bidirectional"))
    )
    (net (code "67") (name "SCK") (class "Default")
      (node (ref "U1") (pin "30") (pinfunction "IO36_30") (pintype "bidirectional"))
    )
    (net (code "68") (name "SCL") (class "Default")
      (node (ref "SCL") (pin "1") (pinfunction "P_1") (pintype "passive"))
      (node (ref "U1") (pin "5") (pinfunction "IO2_5") (pintype "bidirectional"))
    )
    (net (code "69") (name "SDA") (class "Default")
      (node (ref "SDA") (pin "1") (pinfunction "P_1") (pintype "passive"))
      (node (ref "U1") (pin "4") (pinfunction "IO1_4") (pintype "bidirectional"))
    )
    (net (code "70") (name "TX0") (class "Default")
      (node (ref "U1") (pin "37") (pinfunction "U0TXD_37") (pintype "bidirectional"))
      (node (ref "U2") (pin "20") (pinfunction "RXD_20") (pintype "bidirectional"))
    )
    (net (code "71") (name "VIN") (class "Default")
      (node (ref "C7") (pin "1") (pinfunction "1_1") (pintype "passive"))
      (node (ref "D2") (pin "C") (pinfunction "C_C") (pintype "passive"))
      (node (ref "Q1") (pin "2") (pinfunction "S_2") (pintype "passive"))
      (node (ref "R8") (pin "1") (pinfunction "1_1") (pintype "passive"))
      (node (ref "U5") (pin "1") (pinfunction "VIN_1") (pintype "power_in"))
    )
    (net (code "72") (name "V_BATT") (class "Default")
      (node (ref "+") (pin "1") (pinfunction "P_1") (pintype "passive"))
      (node (ref "C6") (pin "1") (pinfunction "1_1") (pintype "passive"))
      (node (ref "Q1") (pin "3") (pinfunction "D_3") (pintype "passive"))
      (node (ref "U4") (pin "3") (pinfunction "VBAT_3") (pintype "power_in"))
    )
    (net (code "73") (name "V_USB") (class "Default")
      (node (ref "C19") (pin "1") (pinfunction "1_1") (pintype "passive"))
      (node (ref "D2") (pin "A") (pinfunction "A_A") (pintype "passive"))
      (node (ref "J1") (pin "1") (pinfunction "VCC_1") (pintype "power_in"))
      (node (ref "Q1") (pin "1") (pinfunction "G_1") (pintype "passive"))
      (node (ref "R3") (pin "1") (pinfunction "1_1") (pintype "passive"))
      (node (ref "R5") (pin "2") (pinfunction "2_2") (pintype "passive"))
      (node (ref "R7") (pin "2") (pinfunction "2_2") (pintype "passive"))
      (node (ref "U4") (pin "4") (pinfunction "VIN_4") (pintype "power_in"))
    )
    (net (code "74") (name "unconnected-(J1-ID-Pad4)") (class "Default")
      (node (ref "J1") (pin "4") (pinfunction "ID_4") (pintype "bidirectional"))
    )
    (net (code "75") (name "unconnected-(LED16-DO-Pad2)") (class "Default")
      (node (ref "LED16") (pin "2") (pinfunction "DO_2") (pintype "bidirectional"))
    )
    (net (code "76") (name "unconnected-(U2-CTS-Pad18)") (class "Default")
      (node (ref "U2") (pin "18") (pinfunction "CTS_18") (pintype "bidirectional"))
    )
    (net (code "77") (name "unconnected-(U2-DCD-Pad24)") (class "Default")
      (node (ref "U2") (pin "24") (pinfunction "DCD_24") (pintype "bidirectional"))
    )
    (net (code "78") (name "unconnected-(U2-DSR-Pad22)") (class "Default")
      (node (ref "U2") (pin "22") (pinfunction "DSR_22") (pintype "bidirectional"))
    )
    (net (code "79") (name "unconnected-(U2-GPIO0{slash}TXT-Pad14)") (class "Default")
      (node (ref "U2") (pin "14") (pinfunction "GPIO0/TXT_14") (pintype "bidirectional"))
    )
    (net (code "80") (name "unconnected-(U2-GPIO1{slash}RXT-Pad13)") (class "Default")
      (node (ref "U2") (pin "13") (pinfunction "GPIO1/RXT_13") (pintype "bidirectional"))
    )
    (net (code "81") (name "unconnected-(U2-GPIO2{slash}RS485-Pad12)") (class "Default")
      (node (ref "U2") (pin "12") (pinfunction "GPIO2/RS485_12") (pintype "bidirectional"))
    )
    (net (code "82") (name "unconnected-(U2-GPIO3{slash}WAKEUP-Pad11)") (class "Default")
      (node (ref "U2") (pin "11") (pinfunction "GPIO3/WAKEUP_11") (pintype "bidirectional"))
    )
    (net (code "83") (name "unconnected-(U2-SUSPEND-Pad17)") (class "Default")
      (node (ref "U2") (pin "17") (pinfunction "SUSPEND_17") (pintype "bidirectional"))
    )
    (net (code "84") (name "unconnected-(U2-SUSPENDB-Pad15)") (class "Default")
      (node (ref "U2") (pin "15") (pinfunction "SUSPENDB_15") (pintype "bidirectional"))
    )
    (net (code "85") (name "unconnected-(U2-~{RI}{slash}CLK-Pad1)") (class "Default")
      (node (ref "U2") (pin "1") (pinfunction "~{RI}/CLK_1") (pintype "bidirectional"))
    )
  )
)
